# Eth_to_SPI.net
KiCad netlist of a schematic drawn in Altium Designer
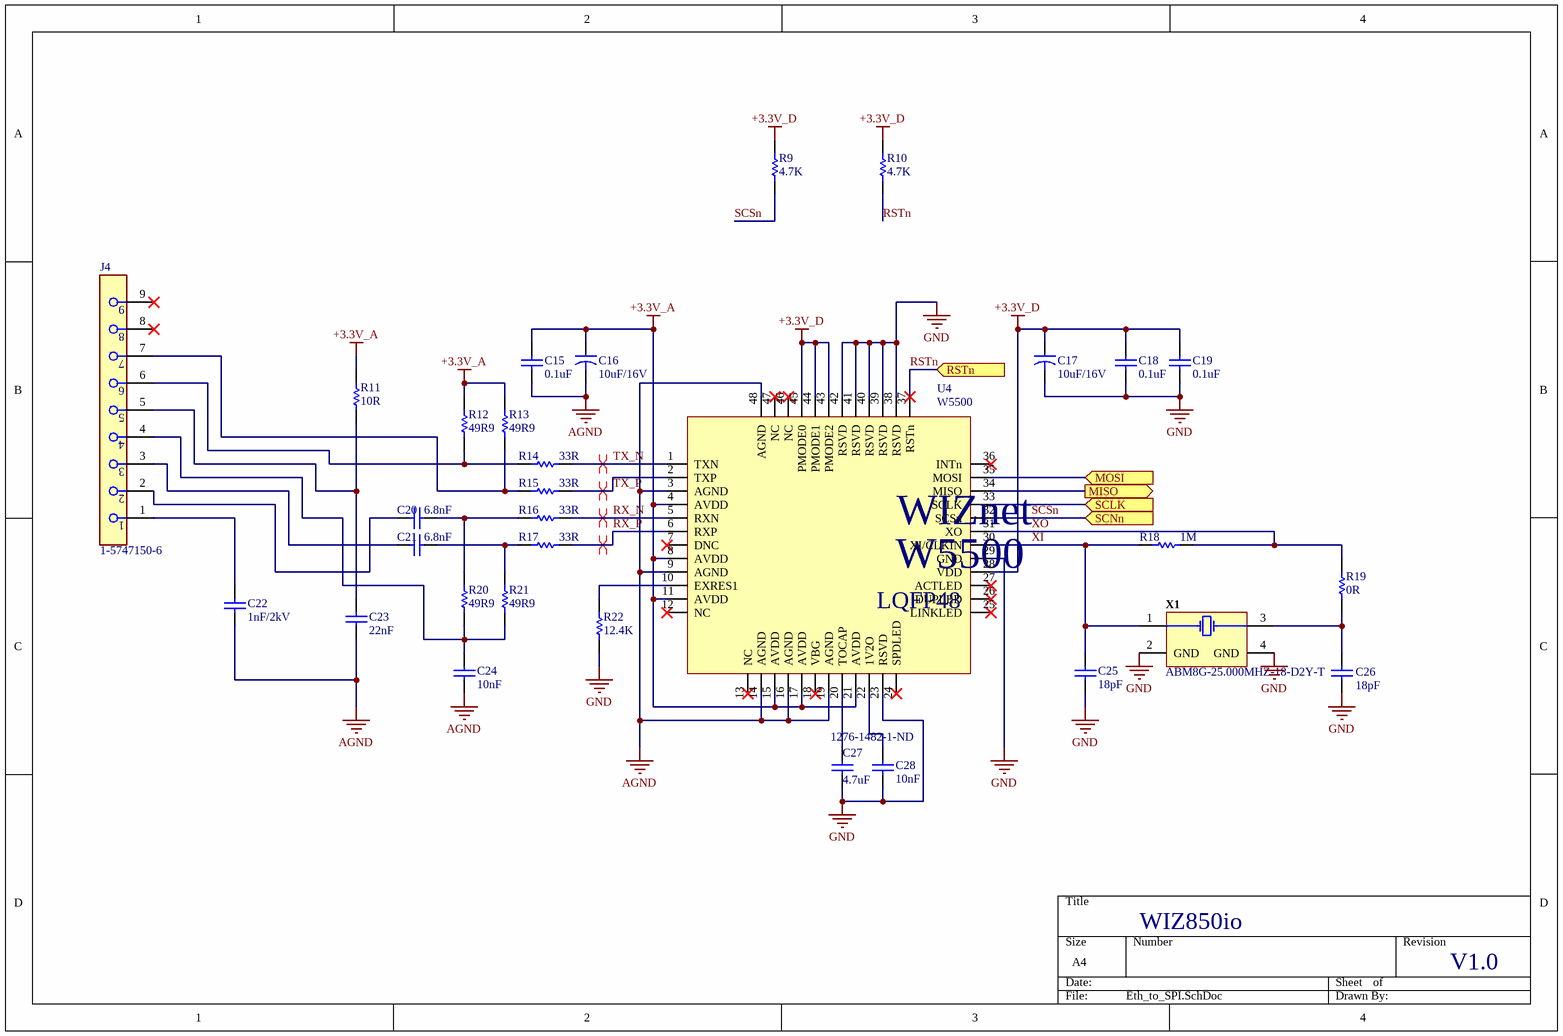
[diagram p0: Eth_to_SPI.SchDoc]

(export (version "E")
  (design (tool "Eeschema 10.0.6"))
  (components
    (comp (ref "C15")
      (value "0.1uF")
      (footprint "J1-0603")
      (description "CAP CER 0.1UF 25V X7R 0603")
      (fields
        (field (name "MANUFACTURER") "Kyocera AVX")
        (field (name "MANUFACTURER PART NUMBER") "06033C104JAT2A")
      )
      (libsource (lib "Scott_lib") (part "CAP-0402"))
    )
    (comp (ref "C16")
      (value "10uF/16V")
      (footprint "10uF 16V")
      (description "Cap Ceramic 10uF 16V X5R 20% SMD 0603 85°C Paper T/R")
      (fields
        (field (name "MANUFACTURER") "Taiyo Yuden")
        (field (name "MANUFACTURER PART NUMBER") "EMK107BBJ106MA-T")
      )
      (libsource (lib "Scott_lib") (part "CAP-A Size"))
    )
    (comp (ref "C17")
      (value "10uF/16V")
      (footprint "10uF 16V")
      (description "Cap Ceramic 10uF 16V X5R 20% SMD 0603 85°C Paper T/R")
      (fields
        (field (name "MANUFACTURER") "Taiyo Yuden")
        (field (name "MANUFACTURER PART NUMBER") "EMK107BBJ106MA-T")
      )
      (libsource (lib "Scott_lib") (part "CAP-A Size"))
    )
    (comp (ref "C18")
      (value "0.1uF")
      (footprint "J1-0603")
      (description "CAP CER 0.1UF 25V X7R 0603")
      (fields
        (field (name "MANUFACTURER") "Kyocera AVX")
        (field (name "MANUFACTURER PART NUMBER") "06033C104JAT2A")
      )
      (libsource (lib "Scott_lib") (part "CAP-0402"))
    )
    (comp (ref "C19")
      (value "0.1uF")
      (footprint "J1-0603")
      (description "CAP CER 0.1UF 25V X7R 0603")
      (fields
        (field (name "MANUFACTURER") "Kyocera AVX")
        (field (name "MANUFACTURER PART NUMBER") "06033C104JAT2A")
      )
      (libsource (lib "Scott_lib") (part "CAP-0402"))
    )
    (comp (ref "C20")
      (value "6.8nF")
      (footprint "6.8nF")
      (fields
        (field (name "MANUFACTURER") "Kyocera AVX")
        (field (name "MANUFACTURER PART NUMBER") "06031C682KAT2A")
        (field (name "TOLERANCE") "10%")
      )
      (libsource (lib "Scott_lib") (part "CAP-0402"))
    )
    (comp (ref "C21")
      (value "6.8nF")
      (footprint "6.8nF")
      (fields
        (field (name "MANUFACTURER") "Kyocera AVX")
        (field (name "MANUFACTURER PART NUMBER") "06031C682KAT2A")
        (field (name "TOLERANCE") "10%")
      )
      (libsource (lib "Scott_lib") (part "CAP-0402"))
    )
    (comp (ref "C22")
      (value "1nF/2kV")
      (footprint "1nF/2kV")
      (description "Cap Ceramic 0.001uF 50V X7R 10% SMD 0603 125C Paper T/R")
      (fields
        (field (name "MANUFACTURER") "Kyocera AVX")
        (field (name "MANUFACTURER PART NUMBER") "06035C102KAT2A")
      )
      (libsource (lib "Scott_lib") (part "CAP-1808"))
    )
    (comp (ref "C23")
      (value "22nF")
      (footprint "22nF")
      (description "Cap Ceramic 0.022uF 25V X7R 10% SMD 0603 125°C Paper T/R")
      (fields
        (field (name "MANUFACTURER") "Kyocera AVX")
        (field (name "MANUFACTURER PART NUMBER") "06033C223KAT2A")
      )
      (libsource (lib "Scott_lib") (part "CAP-0402"))
    )
    (comp (ref "C24")
      (value "10nF")
      (footprint "10nF")
      (description "0603 10nF 50 V ±10 % Tolerance X7R Surface Mount Multilayer Ceramic Capacitor")
      (fields
        (field (name "MANUFACTURER") "Kyocera AVX")
        (field (name "MANUFACTURER PART NUMBER") "06035C103KAT2A")
      )
      (libsource (lib "Scott_lib") (part "CAP-0402"))
    )
    (comp (ref "C25")
      (value "18pF")
      (footprint "18pF")
      (fields
        (field (name "MANUFACTURER") "Kyocera AVX")
        (field (name "MANUFACTURER PART NUMBER") "06031A180JAT2A")
        (field (name "TOLERANCE") "5%")
      )
      (libsource (lib "Scott_lib") (part "CAP-0402"))
    )
    (comp (ref "C26")
      (value "18pF")
      (footprint "18pF")
      (fields
        (field (name "MANUFACTURER") "Kyocera AVX")
        (field (name "MANUFACTURER PART NUMBER") "06031A180JAT2A")
        (field (name "TOLERANCE") "5%")
      )
      (libsource (lib "Scott_lib") (part "CAP-0402"))
    )
    (comp (ref "C27")
      (value "4.7uF")
      (footprint "4.7 uF")
      (description "CAP CER 4.7UF 10V X5R 0402")
      (fields
        (field (name "SUPPLIER PART NUMBER 1") "1276-1482-1-ND")
        (field (name "MANUFACTURER") "Samsung")
        (field (name "MANUFACTURER PART NUMBER") "CL05A475MP5NRNC")
      )
      (libsource (lib "Scott_lib") (part "CAP-0402"))
    )
    (comp (ref "C28")
      (value "10nF")
      (footprint "10nF")
      (description "0603 10nF 50 V ±10 % Tolerance X7R Surface Mount Multilayer Ceramic Capacitor")
      (fields
        (field (name "MANUFACTURER") "Kyocera AVX")
        (field (name "MANUFACTURER PART NUMBER") "06035C103KAT2A")
      )
      (libsource (lib "Scott_lib") (part "CAP-0805"))
    )
    (comp (ref "J4")
      (value "1-5747150-6")
      (footprint "FP-1-5747150-6-MFG")
      (description "CONN D-SUB RCPT 9POS VERT SOLDER")
      (fields
        (field (name "OCTOPART") "https://octopart.com/1-5747150-6-te+connectivity-39500344")
        (field (name "MANUFACTURER") "TE Connectivity")
      )
      (libsource (lib "Altium Content Vault") (part "deee9d0d87fff07c08bdfa5b86cd5a5"))
    )
    (comp (ref "R9")
      (value "4.7K")
      (footprint "4.7k OHM R")
      (description "SMD Resistor, Thick film 4.7 kOhm,  ±  1 %, 0603, CRCW06034K70FKEA, Vishay")
      (fields
        (field (name "MANUFACTURER") "Vishay Dale")
        (field (name "MANUFACTURER PART NUMBER") "CRA06S0434K70JTA")
      )
      (libsource (lib "Scott_lib") (part "RES-0402"))
    )
    (comp (ref "R10")
      (value "4.7K")
      (footprint "4.7k OHM R")
      (description "SMD Resistor, Thick film 4.7 kOhm,  ±  1 %, 0603, CRCW06034K70FKEA, Vishay")
      (fields
        (field (name "MANUFACTURER") "Vishay")
        (field (name "MANUFACTURER PART NUMBER") "CRCW12064K70FKEA")
      )
      (libsource (lib "Scott_lib") (part "RES-0402"))
    )
    (comp (ref "R11")
      (value "10R")
      (footprint "10OHM R")
      (description "Res Thick Film 0603 10 Ohm 1% 1/10W ±100ppm/°C Molded SMD Paper T/R")
      (fields
        (field (name "MANUFACTURER") "Vishay Dale")
        (field (name "MANUFACTURER PART NUMBER") "CRA06S04310R0JTA")
      )
      (libsource (lib "Scott_lib") (part "RES-0402"))
    )
    (comp (ref "R12")
      (value "49R9")
      (footprint "49R9 OHM")
      (description "VISHAY - TNPW060349R9BEEA. - TNPW0603 49R9 0.1% T-9 ET1 E3 ROHS COMPLIANT: YES")
      (fields
        (field (name "MANUFACTURER") "Vishay Dale")
        (field (name "MANUFACTURER PART NUMBER") "CRA06S04349R9FTA")
      )
      (libsource (lib "Scott_lib") (part "RES-0402"))
    )
    (comp (ref "R13")
      (value "49R9")
      (footprint "49R9 OHM")
      (description "VISHAY - TNPW060349R9BEEA. - TNPW0603 49R9 0.1% T-9 ET1 E3 ROHS COMPLIANT: YES")
      (fields
        (field (name "MANUFACTURER") "Vishay Dale")
        (field (name "MANUFACTURER PART NUMBER") "CRA06S04349R9FTA")
      )
      (libsource (lib "Scott_lib") (part "RES-0402"))
    )
    (comp (ref "R14")
      (value "33R")
      (footprint "33OHM R")
      (fields
        (field (name "MANUFACTURER") "Vishay Dale")
        (field (name "MANUFACTURER PART NUMBER") "CRA06S04333R0JTA")
        (field (name "TOLERANCE") "5%")
      )
      (libsource (lib "Scott_lib") (part "RES-0402"))
    )
    (comp (ref "R15")
      (value "33R")
      (footprint "33OHM R")
      (fields
        (field (name "MANUFACTURER") "Vishay Dale")
        (field (name "MANUFACTURER PART NUMBER") "CRA06S04333R0JTA")
        (field (name "TOLERANCE") "5%")
      )
      (libsource (lib "Scott_lib") (part "RES-0402"))
    )
    (comp (ref "R16")
      (value "33R")
      (footprint "33OHM R")
      (fields
        (field (name "MANUFACTURER") "Vishay Dale")
        (field (name "MANUFACTURER PART NUMBER") "CRA06S04333R0JTA")
        (field (name "TOLERANCE") "5%")
      )
      (libsource (lib "Scott_lib") (part "RES-0402"))
    )
    (comp (ref "R17")
      (value "33R")
      (footprint "33OHM R")
      (fields
        (field (name "MANUFACTURER") "Vishay Dale")
        (field (name "MANUFACTURER PART NUMBER") "CRA06S04333R0JTA")
        (field (name "TOLERANCE") "5%")
      )
      (libsource (lib "Scott_lib") (part "RES-0402"))
    )
    (comp (ref "R18")
      (value "1M")
      (footprint "1M OHM R")
      (description "Thick Film Chip Resistor")
      (fields
        (field (name "MANUFACTURER") "Vishay Dale")
        (field (name "MANUFACTURER PART NUMBER") "CRA06S0431M00JTA")
      )
      (libsource (lib "Scott_lib") (part "RES-0402"))
    )
    (comp (ref "R19")
      (value "0R")
      (footprint "0 OHM R")
      (description "Resistor SMD 0 Ohm 0603 PU=5000 ST, CRCW06030000Z0EA, Vishay")
      (fields
        (field (name "MANUFACTURER") "Vishay")
        (field (name "MANUFACTURER PART NUMBER") "CRCW0603-0000Z0EA")
      )
      (libsource (lib "Scott_lib") (part "RES-0402"))
    )
    (comp (ref "R20")
      (value "49R9")
      (footprint "49R9 OHM")
      (description "VISHAY - TNPW060349R9BEEA. - TNPW0603 49R9 0.1% T-9 ET1 E3 ROHS COMPLIANT: YES")
      (fields
        (field (name "MANUFACTURER") "Vishay Dale")
        (field (name "MANUFACTURER PART NUMBER") "CRA06S04349R9FTA")
      )
      (libsource (lib "Scott_lib") (part "RES-0402"))
    )
    (comp (ref "R21")
      (value "49R9")
      (footprint "49R9 OHM")
      (description "VISHAY - TNPW060349R9BEEA. - TNPW0603 49R9 0.1% T-9 ET1 E3 ROHS COMPLIANT: YES")
      (fields
        (field (name "MANUFACTURER") "Vishay Dale")
        (field (name "MANUFACTURER PART NUMBER") "CRA06S04349R9FTA")
      )
      (libsource (lib "Scott_lib") (part "RES-0402"))
    )
    (comp (ref "R22")
      (value "12.4K")
      (footprint "12.4k OHM R")
      (description "Res Thick Film 0603 12.4K Ohm 1% 1/10W ±100ppm/°C Molded SMD SMD Paper T/R")
      (fields
        (field (name "MANUFACTURER") "Vishay")
        (field (name "MANUFACTURER PART NUMBER") "CRCW0603-12K4FKEA")
      )
      (libsource (lib "Scott_lib") (part "RES-0402"))
    )
    (comp (ref "U4")
      (value "W5500")
      (footprint "QFP50P900X900X160-48N")
      (description "Ethernet CTLR Single Chip 10Mbps/100Mbps 3.3V 48-Pin LQFP Reel")
      (fields (field (name "MANUFACTURER") "WIZnet"))
      (libsource (lib "WIZnet Open-source Hardware Library V1.0") (part "W5500"))
    )
    (comp (ref "X1")
      (value "ABM8G-25.000MHZ-18-D2Y-T")
      (footprint "ABRA-ABM8G_V")
      (fields (field (name "MANUFACTURER") "ABRACON") (field (name "TOLERANCE") "20PPM"))
      (libsource (lib "Altium Content Vault") (part "XTAL-1-3-4"))
    )
  )
  (nets
    (net (code "1") (name "+3.3V_A") (class "Default")
      (node (ref "C15") (pin "2") (pinfunction "2_2") (pintype "passive"))
      (node (ref "C16") (pin "1") (pinfunction "1_1") (pintype "passive"))
      (node (ref "R11") (pin "2") (pinfunction "2_2") (pintype "passive"))
      (node (ref "R12") (pin "2") (pinfunction "2_2") (pintype "passive"))
      (node (ref "R13") (pin "2") (pinfunction "2_2") (pintype "passive"))
      (node (ref "U4") (pin "11") (pinfunction "AVDD_11") (pintype "passive"))
      (node (ref "U4") (pin "15") (pinfunction "AVDD_15") (pintype "passive"))
      (node (ref "U4") (pin "17") (pinfunction "AVDD_17") (pintype "passive"))
      (node (ref "U4") (pin "21") (pinfunction "AVDD_21") (pintype "passive"))
      (node (ref "U4") (pin "4") (pinfunction "AVDD_4") (pintype "passive"))
      (node (ref "U4") (pin "8") (pinfunction "AVDD_8") (pintype "passive"))
    )
    (net (code "2") (name "+3.3V_D") (class "Default")
      (node (ref "C17") (pin "1") (pinfunction "1_1") (pintype "passive"))
      (node (ref "C18") (pin "2") (pinfunction "2_2") (pintype "passive"))
      (node (ref "C19") (pin "2") (pinfunction "2_2") (pintype "passive"))
      (node (ref "R10") (pin "2") (pinfunction "2_2") (pintype "passive"))
      (node (ref "R9") (pin "2") (pinfunction "2_2") (pintype "passive"))
      (node (ref "U4") (pin "28") (pinfunction "VDD_28") (pintype "passive"))
      (node (ref "U4") (pin "43") (pinfunction "PMODE2_43") (pintype "passive"))
      (node (ref "U4") (pin "44") (pinfunction "PMODE1_44") (pintype "passive"))
      (node (ref "U4") (pin "45") (pinfunction "PMODE0_45") (pintype "passive"))
    )
    (net (code "3") (name "/MISO") (class "Default")
      (node (ref "U4") (pin "34") (pinfunction "MISO_34") (pintype "passive"))
    )
    (net (code "4") (name "/MOSI") (class "Default")
      (node (ref "U4") (pin "35") (pinfunction "MOSI_35") (pintype "passive"))
    )
    (net (code "5") (name "/RSTn") (class "Default")
      (node (ref "R10") (pin "1") (pinfunction "1_1") (pintype "passive"))
      (node (ref "U4") (pin "37") (pinfunction "RSTn_37") (pintype "passive"))
    )
    (net (code "6") (name "/RX_N") (class "Default")
      (node (ref "R16") (pin "2") (pinfunction "2_2") (pintype "passive"))
      (node (ref "U4") (pin "5") (pinfunction "RXN_5") (pintype "passive"))
    )
    (net (code "7") (name "/RX_P") (class "Default")
      (node (ref "R17") (pin "2") (pinfunction "2_2") (pintype "passive"))
      (node (ref "U4") (pin "6") (pinfunction "RXP_6") (pintype "passive"))
    )
    (net (code "8") (name "/SCLK") (class "Default")
      (node (ref "U4") (pin "33") (pinfunction "SCLK_33") (pintype "passive"))
    )
    (net (code "9") (name "/SCSn") (class "Default")
      (node (ref "R9") (pin "1") (pinfunction "1_1") (pintype "passive"))
      (node (ref "U4") (pin "32") (pinfunction "SCSn_32") (pintype "passive"))
    )
    (net (code "10") (name "/TX_N") (class "Default")
      (node (ref "R14") (pin "2") (pinfunction "2_2") (pintype "passive"))
      (node (ref "U4") (pin "1") (pinfunction "TXN_1") (pintype "passive"))
    )
    (net (code "11") (name "/TX_P") (class "Default")
      (node (ref "R15") (pin "2") (pinfunction "2_2") (pintype "passive"))
      (node (ref "U4") (pin "2") (pinfunction "TXP_2") (pintype "passive"))
    )
    (net (code "12") (name "/XI") (class "Default")
      (node (ref "C25") (pin "2") (pinfunction "2_2") (pintype "passive"))
      (node (ref "R18") (pin "1") (pinfunction "1_1") (pintype "passive"))
      (node (ref "U4") (pin "30") (pinfunction "XI/CLKIN_30") (pintype "passive"))
      (node (ref "X1") (pin "1") (pinfunction "X1_1") (pintype "passive"))
    )
    (net (code "13") (name "/XO") (class "Default")
      (node (ref "R18") (pin "2") (pinfunction "2_2") (pintype "passive"))
      (node (ref "R19") (pin "2") (pinfunction "2_2") (pintype "passive"))
      (node (ref "U4") (pin "31") (pinfunction "XO_31") (pintype "passive"))
    )
    (net (code "14") (name "AGND") (class "Default")
      (node (ref "C15") (pin "1") (pinfunction "1_1") (pintype "passive"))
      (node (ref "C16") (pin "2") (pinfunction "2_2") (pintype "passive"))
      (node (ref "C22") (pin "2") (pinfunction "2_2") (pintype "passive"))
      (node (ref "C23") (pin "1") (pinfunction "1_1") (pintype "passive"))
      (node (ref "C24") (pin "1") (pinfunction "1_1") (pintype "passive"))
      (node (ref "U4") (pin "14") (pinfunction "AGND_14") (pintype "passive"))
      (node (ref "U4") (pin "16") (pinfunction "AGND_16") (pintype "passive"))
      (node (ref "U4") (pin "19") (pinfunction "AGND_19") (pintype "passive"))
      (node (ref "U4") (pin "3") (pinfunction "AGND_3") (pintype "passive"))
      (node (ref "U4") (pin "48") (pinfunction "AGND_48") (pintype "passive"))
      (node (ref "U4") (pin "9") (pinfunction "AGND_9") (pintype "passive"))
    )
    (net (code "15") (name "GND") (class "Default")
      (node (ref "C17") (pin "2") (pinfunction "2_2") (pintype "passive"))
      (node (ref "C18") (pin "1") (pinfunction "1_1") (pintype "passive"))
      (node (ref "C19") (pin "1") (pinfunction "1_1") (pintype "passive"))
      (node (ref "C25") (pin "1") (pinfunction "1_1") (pintype "passive"))
      (node (ref "C26") (pin "1") (pinfunction "1_1") (pintype "passive"))
      (node (ref "C27") (pin "1") (pinfunction "1_1") (pintype "passive"))
      (node (ref "C28") (pin "1") (pinfunction "1_1") (pintype "passive"))
      (node (ref "R22") (pin "1") (pinfunction "1_1") (pintype "passive"))
      (node (ref "U4") (pin "23") (pinfunction "RSVD_23") (pintype "passive"))
      (node (ref "U4") (pin "29") (pinfunction "GND_29") (pintype "passive"))
      (node (ref "U4") (pin "38") (pinfunction "RSVD_38") (pintype "passive"))
      (node (ref "U4") (pin "39") (pinfunction "RSVD_39") (pintype "passive"))
      (node (ref "U4") (pin "40") (pinfunction "RSVD_40") (pintype "passive"))
      (node (ref "U4") (pin "41") (pinfunction "RSVD_41") (pintype "passive"))
      (node (ref "U4") (pin "42") (pinfunction "RSVD_42") (pintype "passive"))
      (node (ref "X1") (pin "2") (pinfunction "GND_2") (pintype "power_in"))
      (node (ref "X1") (pin "4") (pinfunction "GND_4") (pintype "power_in"))
    )
    (net (code "16") (name "Net-(C20-Pad1)") (class "Default")
      (node (ref "C20") (pin "1") (pinfunction "1_1") (pintype "passive"))
      (node (ref "J4") (pin "2") (pinfunction "2_2") (pintype "passive"))
    )
    (net (code "17") (name "Net-(C20-Pad2)") (class "Default")
      (node (ref "C20") (pin "2") (pinfunction "2_2") (pintype "passive"))
      (node (ref "R16") (pin "1") (pinfunction "1_1") (pintype "passive"))
      (node (ref "R20") (pin "2") (pinfunction "2_2") (pintype "passive"))
    )
    (net (code "18") (name "Net-(C21-Pad1)") (class "Default")
      (node (ref "C21") (pin "1") (pinfunction "1_1") (pintype "passive"))
      (node (ref "J4") (pin "3") (pinfunction "3_3") (pintype "passive"))
    )
    (net (code "19") (name "Net-(C21-Pad2)") (class "Default")
      (node (ref "C21") (pin "2") (pinfunction "2_2") (pintype "passive"))
      (node (ref "R17") (pin "1") (pinfunction "1_1") (pintype "passive"))
      (node (ref "R21") (pin "2") (pinfunction "2_2") (pintype "passive"))
    )
    (net (code "20") (name "Net-(C22-Pad1)") (class "Default")
      (node (ref "C22") (pin "1") (pinfunction "1_1") (pintype "passive"))
      (node (ref "J4") (pin "1") (pinfunction "1_1") (pintype "passive"))
    )
    (net (code "21") (name "Net-(C23-Pad2)") (class "Default")
      (node (ref "C23") (pin "2") (pinfunction "2_2") (pintype "passive"))
      (node (ref "J4") (pin "5") (pinfunction "5_5") (pintype "passive"))
      (node (ref "R11") (pin "1") (pinfunction "1_1") (pintype "passive"))
    )
    (net (code "22") (name "Net-(C24-Pad2)") (class "Default")
      (node (ref "C24") (pin "2") (pinfunction "2_2") (pintype "passive"))
      (node (ref "J4") (pin "4") (pinfunction "4_4") (pintype "passive"))
      (node (ref "R20") (pin "1") (pinfunction "1_1") (pintype "passive"))
      (node (ref "R21") (pin "1") (pinfunction "1_1") (pintype "passive"))
    )
    (net (code "23") (name "Net-(J4-Pad6)") (class "Default")
      (node (ref "J4") (pin "6") (pinfunction "6_6") (pintype "passive"))
      (node (ref "R12") (pin "1") (pinfunction "1_1") (pintype "passive"))
      (node (ref "R14") (pin "1") (pinfunction "1_1") (pintype "passive"))
    )
    (net (code "24") (name "Net-(J4-Pad7)") (class "Default")
      (node (ref "J4") (pin "7") (pinfunction "7_7") (pintype "passive"))
      (node (ref "R13") (pin "1") (pinfunction "1_1") (pintype "passive"))
      (node (ref "R15") (pin "1") (pinfunction "1_1") (pintype "passive"))
    )
    (net (code "25") (name "Net-(U4-1V2O)") (class "Default")
      (node (ref "C28") (pin "2") (pinfunction "2_2") (pintype "passive"))
      (node (ref "U4") (pin "22") (pinfunction "1V2O_22") (pintype "passive"))
    )
    (net (code "26") (name "Net-(U4-EXRES1)") (class "Default")
      (node (ref "R22") (pin "2") (pinfunction "2_2") (pintype "passive"))
      (node (ref "U4") (pin "10") (pinfunction "EXRES1_10") (pintype "passive"))
    )
    (net (code "27") (name "Net-(U4-TOCAP)") (class "Default")
      (node (ref "C27") (pin "2") (pinfunction "2_2") (pintype "passive"))
      (node (ref "U4") (pin "20") (pinfunction "TOCAP_20") (pintype "passive"))
    )
    (net (code "28") (name "Net-(X1-X2)") (class "Default")
      (node (ref "C26") (pin "2") (pinfunction "2_2") (pintype "passive"))
      (node (ref "R19") (pin "1") (pinfunction "1_1") (pintype "passive"))
      (node (ref "X1") (pin "3") (pinfunction "X2_3") (pintype "passive"))
    )
    (net (code "29") (name "unconnected-(J4-Pad8)") (class "Default")
      (node (ref "J4") (pin "8") (pinfunction "8_8") (pintype "passive+no_connect"))
    )
    (net (code "30") (name "unconnected-(J4-Pad9)") (class "Default")
      (node (ref "J4") (pin "9") (pinfunction "9_9") (pintype "passive+no_connect"))
    )
    (net (code "31") (name "unconnected-(U4-ACTLED-Pad27)") (class "Default")
      (node (ref "U4") (pin "27") (pinfunction "ACTLED_27") (pintype "passive+no_connect"))
    )
    (net (code "32") (name "unconnected-(U4-DNC-Pad7)") (class "Default")
      (node (ref "U4") (pin "7") (pinfunction "DNC_7") (pintype "passive+no_connect"))
    )
    (net (code "33") (name "unconnected-(U4-DUPLED-Pad26)") (class "Default")
      (node (ref "U4") (pin "26") (pinfunction "DUPLED_26") (pintype "passive+no_connect"))
    )
    (net (code "34") (name "unconnected-(U4-INTn-Pad36)") (class "Default")
      (node (ref "U4") (pin "36") (pinfunction "INTn_36") (pintype "passive+no_connect"))
    )
    (net (code "35") (name "unconnected-(U4-LINKLED-Pad25)") (class "Default")
      (node (ref "U4") (pin "25") (pinfunction "LINKLED_25") (pintype "passive+no_connect"))
    )
    (net (code "36") (name "unconnected-(U4-NC-Pad12)") (class "Default")
      (node (ref "U4") (pin "12") (pinfunction "NC_12") (pintype "passive+no_connect"))
    )
    (net (code "37") (name "unconnected-(U4-NC-Pad13)") (class "Default")
      (node (ref "U4") (pin "13") (pinfunction "NC_13") (pintype "passive+no_connect"))
    )
    (net (code "38") (name "unconnected-(U4-NC-Pad46)") (class "Default")
      (node (ref "U4") (pin "46") (pinfunction "NC_46") (pintype "passive+no_connect"))
    )
    (net (code "39") (name "unconnected-(U4-NC-Pad47)") (class "Default")
      (node (ref "U4") (pin "47") (pinfunction "NC_47") (pintype "passive+no_connect"))
    )
    (net (code "40") (name "unconnected-(U4-SPDLED-Pad24)") (class "Default")
      (node (ref "U4") (pin "24") (pinfunction "SPDLED_24") (pintype "passive+no_connect"))
    )
    (net (code "41") (name "unconnected-(U4-VBG-Pad18)") (class "Default")
      (node (ref "U4") (pin "18") (pinfunction "VBG_18") (pintype "passive+no_connect"))
    )
  )
)
